# M227X.net
KiCad netlist of a schematic drawn in EAGLE
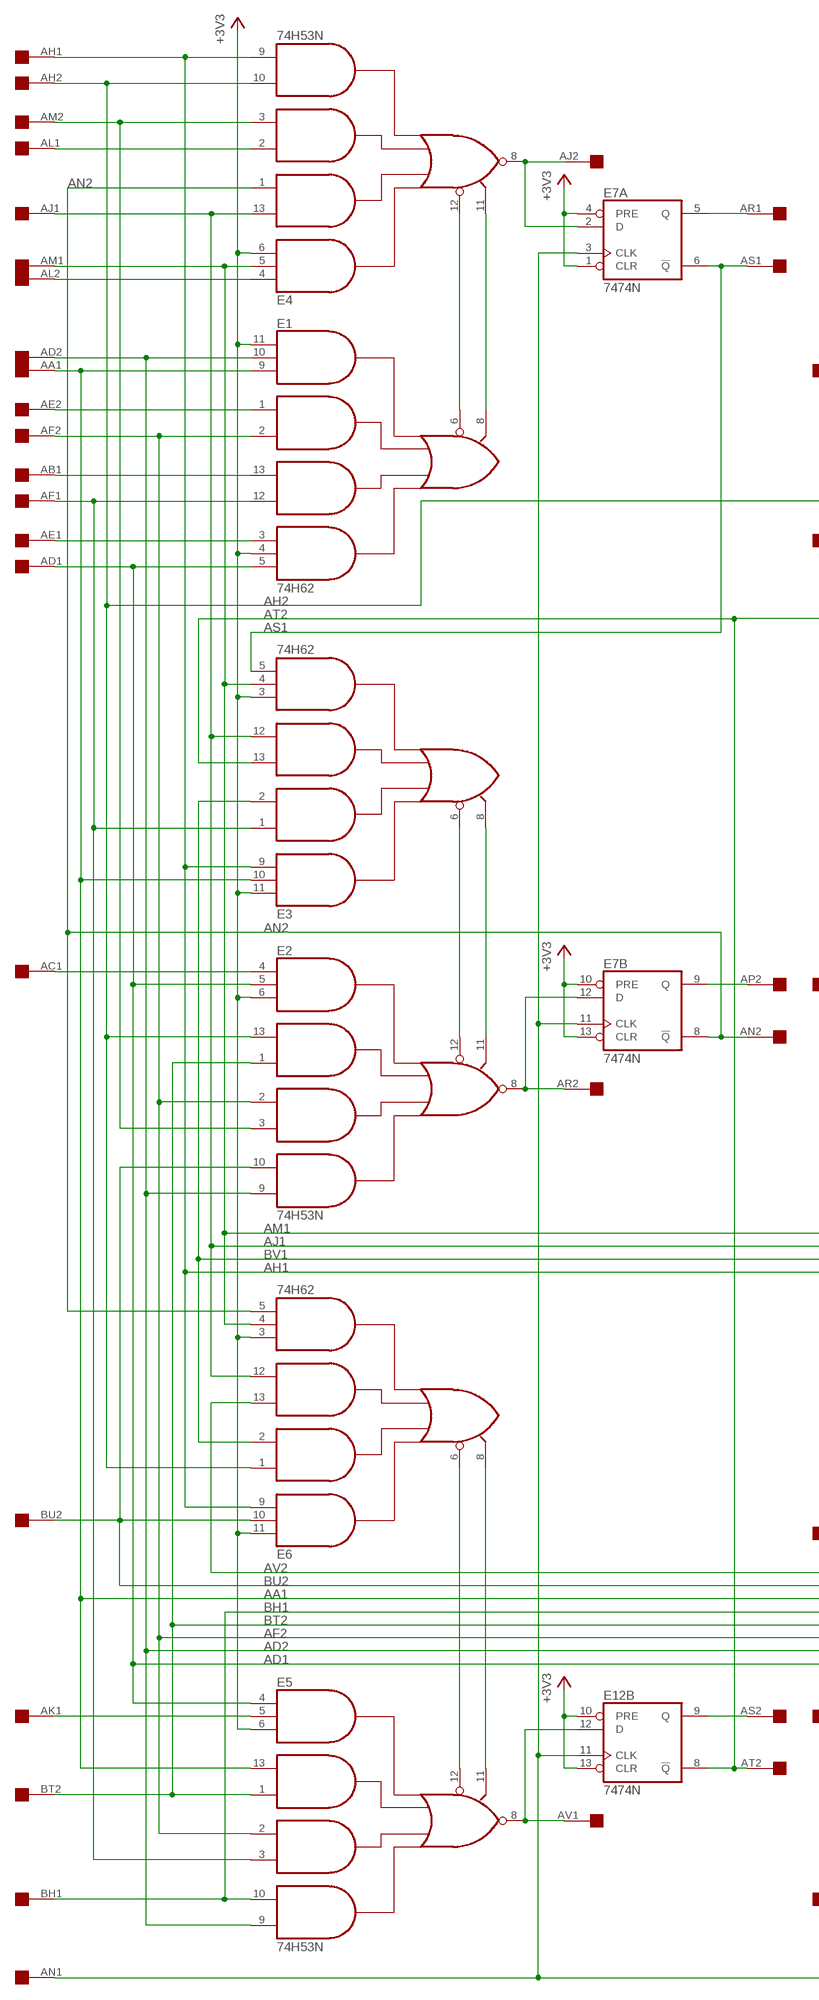
[diagram p0: schematic, sheet 1, part 1 of 2]
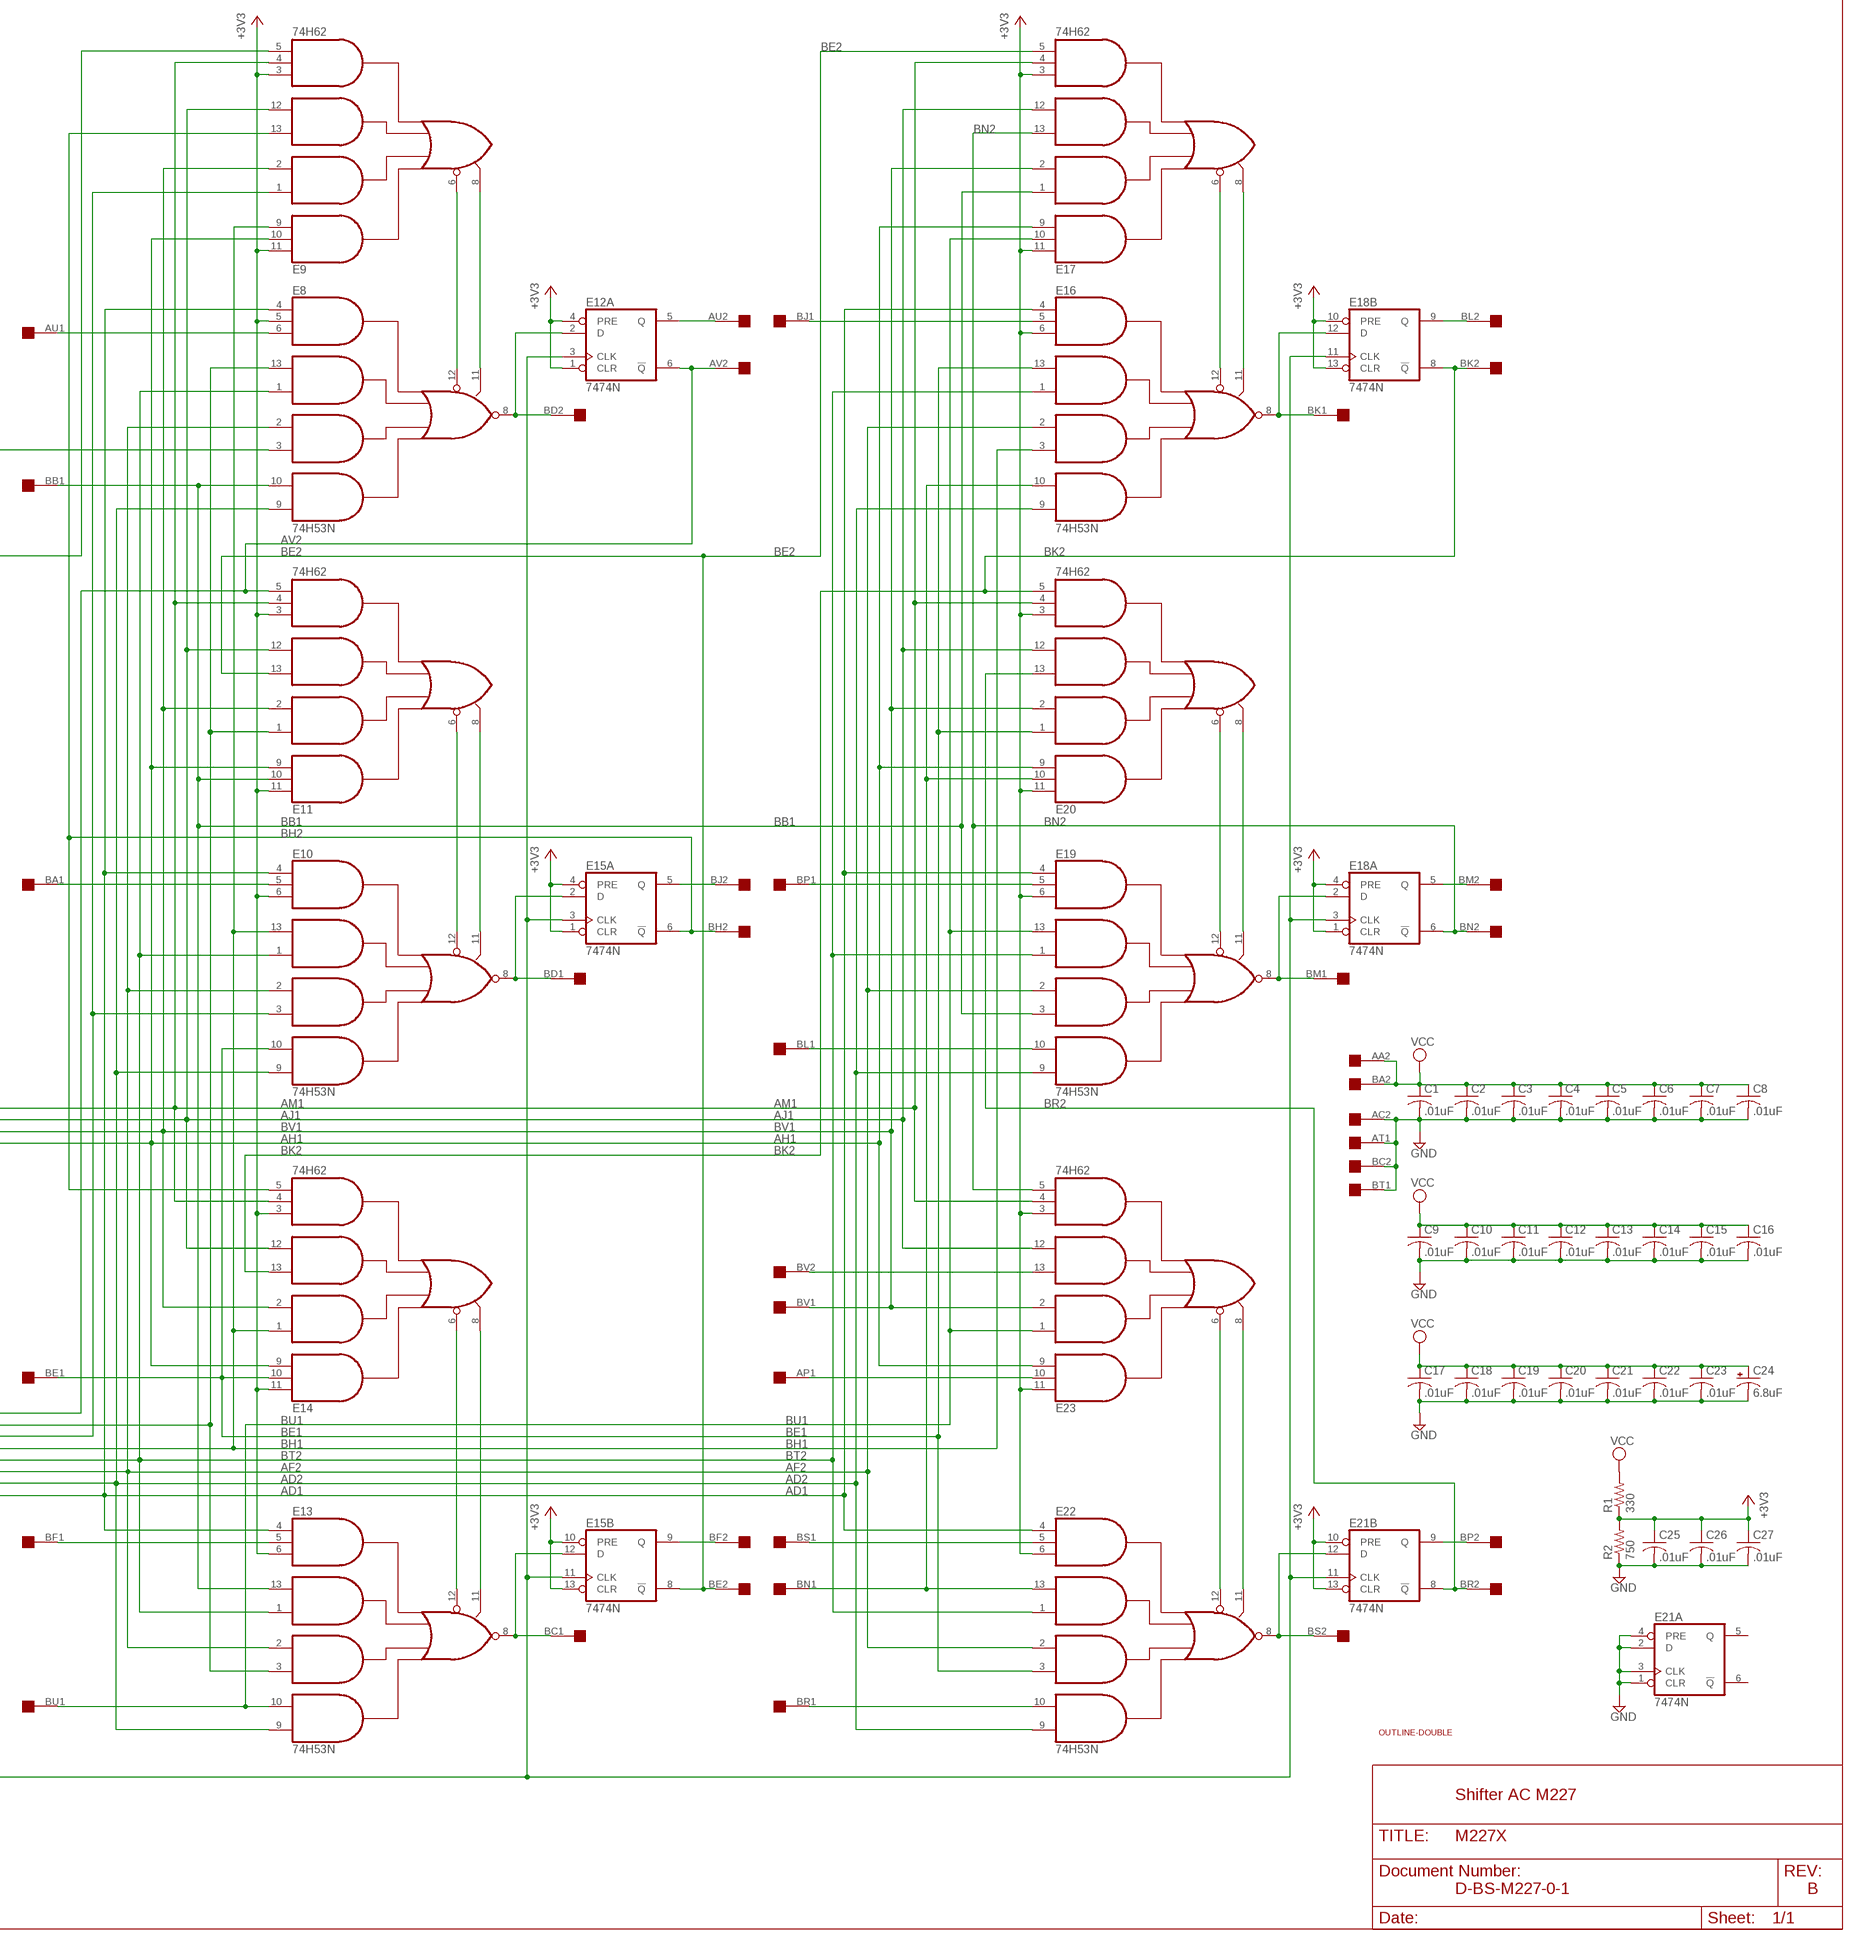
[diagram p1: schematic, sheet 1, part 2 of 2]

(export (version "E")
  (design (tool "Eeschema 10.0.6"))
  (components
    (comp (ref "C1")
      (value ".01uF")
      (footprint "eagle-import:C050-025X075")
      (libsource (lib "eagle-import") (part "C-US050-025X075"))
    )
    (comp (ref "C2")
      (value ".01uF")
      (footprint "eagle-import:C050-025X075")
      (libsource (lib "eagle-import") (part "C-US050-025X075"))
    )
    (comp (ref "C3")
      (value ".01uF")
      (footprint "eagle-import:C050-025X075")
      (libsource (lib "eagle-import") (part "C-US050-025X075"))
    )
    (comp (ref "C4")
      (value ".01uF")
      (footprint "eagle-import:C050-025X075")
      (libsource (lib "eagle-import") (part "C-US050-025X075"))
    )
    (comp (ref "C5")
      (value ".01uF")
      (footprint "eagle-import:C050-025X075")
      (libsource (lib "eagle-import") (part "C-US050-025X075"))
    )
    (comp (ref "C6")
      (value ".01uF")
      (footprint "eagle-import:C050-025X075")
      (libsource (lib "eagle-import") (part "C-US050-025X075"))
    )
    (comp (ref "C7")
      (value ".01uF")
      (footprint "eagle-import:C050-025X075")
      (libsource (lib "eagle-import") (part "C-US050-025X075"))
    )
    (comp (ref "C8")
      (value ".01uF")
      (footprint "eagle-import:C050-025X075")
      (libsource (lib "eagle-import") (part "C-US050-025X075"))
    )
    (comp (ref "C9")
      (value ".01uF")
      (footprint "eagle-import:C050-025X075")
      (libsource (lib "eagle-import") (part "C-US050-025X075"))
    )
    (comp (ref "C10")
      (value ".01uF")
      (footprint "eagle-import:C050-025X075")
      (libsource (lib "eagle-import") (part "C-US050-025X075"))
    )
    (comp (ref "C11")
      (value ".01uF")
      (footprint "eagle-import:C050-025X075")
      (libsource (lib "eagle-import") (part "C-US050-025X075"))
    )
    (comp (ref "C12")
      (value ".01uF")
      (footprint "eagle-import:C050-025X075")
      (libsource (lib "eagle-import") (part "C-US050-025X075"))
    )
    (comp (ref "C13")
      (value ".01uF")
      (footprint "eagle-import:C050-025X075")
      (libsource (lib "eagle-import") (part "C-US050-025X075"))
    )
    (comp (ref "C14")
      (value ".01uF")
      (footprint "eagle-import:C050-025X075")
      (libsource (lib "eagle-import") (part "C-US050-025X075"))
    )
    (comp (ref "C15")
      (value ".01uF")
      (footprint "eagle-import:C050-025X075")
      (libsource (lib "eagle-import") (part "C-US050-025X075"))
    )
    (comp (ref "C16")
      (value ".01uF")
      (footprint "eagle-import:C050-025X075")
      (libsource (lib "eagle-import") (part "C-US050-025X075"))
    )
    (comp (ref "C17")
      (value ".01uF")
      (footprint "eagle-import:C050-025X075")
      (libsource (lib "eagle-import") (part "C-US050-025X075"))
    )
    (comp (ref "C18")
      (value ".01uF")
      (footprint "eagle-import:C050-025X075")
      (libsource (lib "eagle-import") (part "C-US050-025X075"))
    )
    (comp (ref "C19")
      (value ".01uF")
      (footprint "eagle-import:C050-025X075")
      (libsource (lib "eagle-import") (part "C-US050-025X075"))
    )
    (comp (ref "C20")
      (value ".01uF")
      (footprint "eagle-import:C050-025X075")
      (libsource (lib "eagle-import") (part "C-US050-025X075"))
    )
    (comp (ref "C21")
      (value ".01uF")
      (footprint "eagle-import:C050-025X075")
      (libsource (lib "eagle-import") (part "C-US050-025X075"))
    )
    (comp (ref "C22")
      (value ".01uF")
      (footprint "eagle-import:C050-025X075")
      (libsource (lib "eagle-import") (part "C-US050-025X075"))
    )
    (comp (ref "C23")
      (value ".01uF")
      (footprint "eagle-import:C050-025X075")
      (libsource (lib "eagle-import") (part "C-US050-025X075"))
    )
    (comp (ref "C24")
      (value "6.8uF")
      (footprint "eagle-import:E12-8")
      (libsource (lib "eagle-import") (part "CPOL-USE20-8AXIAL"))
    )
    (comp (ref "C25")
      (value ".01uF")
      (footprint "eagle-import:C050-025X075")
      (libsource (lib "eagle-import") (part "C-US050-025X075"))
    )
    (comp (ref "C26")
      (value ".01uF")
      (footprint "eagle-import:C050-025X075")
      (libsource (lib "eagle-import") (part "C-US050-025X075"))
    )
    (comp (ref "C27")
      (value ".01uF")
      (footprint "eagle-import:C050-025X075")
      (libsource (lib "eagle-import") (part "C-US050-025X075"))
    )
    (comp (ref "E1")
      (value "74H62")
      (footprint "eagle-import:DIL14")
      (libsource (lib "eagle-import") (part "7462"))
    )
    (comp (ref "E2")
      (value "74H53N")
      (footprint "eagle-import:DIL14")
      (libsource (lib "eagle-import") (part "74H53N"))
    )
    (comp (ref "E3")
      (value "74H62")
      (footprint "eagle-import:DIL14")
      (libsource (lib "eagle-import") (part "7462"))
    )
    (comp (ref "E4")
      (value "74H53N")
      (footprint "eagle-import:DIL14")
      (libsource (lib "eagle-import") (part "74H53N"))
    )
    (comp (ref "E5")
      (value "74H53N")
      (footprint "eagle-import:DIL14")
      (libsource (lib "eagle-import") (part "74H53N"))
    )
    (comp (ref "E6")
      (value "74H62")
      (footprint "eagle-import:DIL14")
      (libsource (lib "eagle-import") (part "7462"))
    )
    (comp (ref "E7")
      (value "7474N")
      (footprint "eagle-import:DIL14")
      (libsource (lib "eagle-import") (part "7474NS"))
    )
    (comp (ref "E8")
      (value "74H53N")
      (footprint "eagle-import:DIL14")
      (libsource (lib "eagle-import") (part "74H53N"))
    )
    (comp (ref "E9")
      (value "74H62")
      (footprint "eagle-import:DIL14")
      (libsource (lib "eagle-import") (part "7462"))
    )
    (comp (ref "E10")
      (value "74H53N")
      (footprint "eagle-import:DIL14")
      (libsource (lib "eagle-import") (part "74H53N"))
    )
    (comp (ref "E11")
      (value "74H62")
      (footprint "eagle-import:DIL14")
      (libsource (lib "eagle-import") (part "7462"))
    )
    (comp (ref "E12")
      (value "7474N")
      (footprint "eagle-import:DIL14")
      (libsource (lib "eagle-import") (part "7474NS"))
    )
    (comp (ref "E13")
      (value "74H53N")
      (footprint "eagle-import:DIL14")
      (libsource (lib "eagle-import") (part "74H53N"))
    )
    (comp (ref "E14")
      (value "74H62")
      (footprint "eagle-import:DIL14")
      (libsource (lib "eagle-import") (part "7462"))
    )
    (comp (ref "E15")
      (value "7474N")
      (footprint "eagle-import:DIL14")
      (libsource (lib "eagle-import") (part "7474NS"))
    )
    (comp (ref "E16")
      (value "74H53N")
      (footprint "eagle-import:DIL14")
      (libsource (lib "eagle-import") (part "74H53N"))
    )
    (comp (ref "E17")
      (value "74H62")
      (footprint "eagle-import:DIL14")
      (libsource (lib "eagle-import") (part "7462"))
    )
    (comp (ref "E18")
      (value "7474N")
      (footprint "eagle-import:DIL14")
      (libsource (lib "eagle-import") (part "7474NS"))
    )
    (comp (ref "E19")
      (value "74H53N")
      (footprint "eagle-import:DIL14")
      (libsource (lib "eagle-import") (part "74H53N"))
    )
    (comp (ref "E20")
      (value "74H62")
      (footprint "eagle-import:DIL14")
      (libsource (lib "eagle-import") (part "7462"))
    )
    (comp (ref "E21")
      (value "7474N")
      (footprint "eagle-import:DIL14")
      (libsource (lib "eagle-import") (part "7474NS"))
    )
    (comp (ref "E22")
      (value "74H53N")
      (footprint "eagle-import:DIL14")
      (libsource (lib "eagle-import") (part "74H53N"))
    )
    (comp (ref "E23")
      (value "74H62")
      (footprint "eagle-import:DIL14")
      (libsource (lib "eagle-import") (part "7462"))
    )
    (comp (ref "R1")
      (value "330")
      (footprint "eagle-import:0207_10")
      (libsource (lib "eagle-import") (part "R-US_0207/10"))
    )
    (comp (ref "R2")
      (value "750")
      (footprint "eagle-import:0207_10")
      (libsource (lib "eagle-import") (part "R-US_0207/10"))
    )
    (comp (ref "U$1")
      (value "OUTLINE-DOUBLE")
      (footprint "eagle-import:DOUBLE")
      (libsource (lib "eagle-import") (part "OUTLINE-DOUBLE"))
    )
    (comp (ref "U$3")
      (value "DOUBLE")
      (footprint "eagle-import:EDGE-CON4")
      (libsource (lib "eagle-import") (part "DOUBLE"))
    )
  )
  (nets
    (net (code "1") (name "+3V3") (class "Default")
      (node (ref "C25") (pin "1") (pinfunction "1_1") (pintype "passive"))
      (node (ref "C26") (pin "1") (pinfunction "1_1") (pintype "passive"))
      (node (ref "C27") (pin "1") (pinfunction "1_1") (pintype "passive"))
      (node (ref "E1") (pin "11") (pinfunction "I1_11") (pintype "input"))
      (node (ref "E1") (pin "4") (pinfunction "I9_4") (pintype "input"))
      (node (ref "E10") (pin "6") (pinfunction "I2_6") (pintype "input"))
      (node (ref "E11") (pin "11") (pinfunction "I1_11") (pintype "input"))
      (node (ref "E11") (pin "3") (pinfunction "I8_3") (pintype "input"))
      (node (ref "E12") (pin "1") (pinfunction "CLR_1") (pintype "input"))
      (node (ref "E12") (pin "10") (pinfunction "PRE_10") (pintype "input"))
      (node (ref "E12") (pin "13") (pinfunction "CLR_13") (pintype "input"))
      (node (ref "E12") (pin "4") (pinfunction "PRE_4") (pintype "input"))
      (node (ref "E13") (pin "6") (pinfunction "I2_6") (pintype "input"))
      (node (ref "E14") (pin "11") (pinfunction "I1_11") (pintype "input"))
      (node (ref "E14") (pin "3") (pinfunction "I8_3") (pintype "input"))
      (node (ref "E15") (pin "1") (pinfunction "CLR_1") (pintype "input"))
      (node (ref "E15") (pin "10") (pinfunction "PRE_10") (pintype "input"))
      (node (ref "E15") (pin "13") (pinfunction "CLR_13") (pintype "input"))
      (node (ref "E15") (pin "4") (pinfunction "PRE_4") (pintype "input"))
      (node (ref "E16") (pin "6") (pinfunction "I2_6") (pintype "input"))
      (node (ref "E17") (pin "11") (pinfunction "I1_11") (pintype "input"))
      (node (ref "E17") (pin "3") (pinfunction "I8_3") (pintype "input"))
      (node (ref "E18") (pin "1") (pinfunction "CLR_1") (pintype "input"))
      (node (ref "E18") (pin "10") (pinfunction "PRE_10") (pintype "input"))
      (node (ref "E18") (pin "13") (pinfunction "CLR_13") (pintype "input"))
      (node (ref "E18") (pin "4") (pinfunction "PRE_4") (pintype "input"))
      (node (ref "E19") (pin "6") (pinfunction "I2_6") (pintype "input"))
      (node (ref "E2") (pin "6") (pinfunction "I2_6") (pintype "input"))
      (node (ref "E20") (pin "11") (pinfunction "I1_11") (pintype "input"))
      (node (ref "E20") (pin "3") (pinfunction "I8_3") (pintype "input"))
      (node (ref "E21") (pin "10") (pinfunction "PRE_10") (pintype "input"))
      (node (ref "E21") (pin "13") (pinfunction "CLR_13") (pintype "input"))
      (node (ref "E22") (pin "6") (pinfunction "I2_6") (pintype "input"))
      (node (ref "E23") (pin "11") (pinfunction "I1_11") (pintype "input"))
      (node (ref "E23") (pin "3") (pinfunction "I8_3") (pintype "input"))
      (node (ref "E3") (pin "11") (pinfunction "I1_11") (pintype "input"))
      (node (ref "E3") (pin "3") (pinfunction "I8_3") (pintype "input"))
      (node (ref "E4") (pin "6") (pinfunction "I2_6") (pintype "input"))
      (node (ref "E5") (pin "6") (pinfunction "I2_6") (pintype "input"))
      (node (ref "E6") (pin "11") (pinfunction "I1_11") (pintype "input"))
      (node (ref "E6") (pin "3") (pinfunction "I8_3") (pintype "input"))
      (node (ref "E7") (pin "1") (pinfunction "CLR_1") (pintype "input"))
      (node (ref "E7") (pin "10") (pinfunction "PRE_10") (pintype "input"))
      (node (ref "E7") (pin "13") (pinfunction "CLR_13") (pintype "input"))
      (node (ref "E7") (pin "4") (pinfunction "PRE_4") (pintype "input"))
      (node (ref "E8") (pin "5") (pinfunction "I11_5") (pintype "input"))
      (node (ref "E9") (pin "11") (pinfunction "I1_11") (pintype "input"))
      (node (ref "E9") (pin "3") (pinfunction "I8_3") (pintype "input"))
      (node (ref "R1") (pin "1") (pinfunction "1_1") (pintype "passive"))
      (node (ref "R2") (pin "2") (pinfunction "2_2") (pintype "passive"))
    )
    (net (code "2") (name "/AA1") (class "Default")
      (node (ref "E1") (pin "9") (pinfunction "I3_9") (pintype "input"))
      (node (ref "E10") (pin "3") (pinfunction "I6_3") (pintype "input"))
      (node (ref "E3") (pin "10") (pinfunction "I2_10") (pintype "input"))
      (node (ref "E5") (pin "13") (pinfunction "I3_13") (pintype "input"))
      (node (ref "E9") (pin "1") (pinfunction "I4_1") (pintype "input"))
      (node (ref "U$3") (pin "AA1") (pinfunction "1_AA1") (pintype "bidirectional"))
    )
    (net (code "3") (name "/AD1") (class "Default")
      (node (ref "E1") (pin "5") (pinfunction "I10_5") (pintype "input"))
      (node (ref "E10") (pin "4") (pinfunction "I1_4") (pintype "input"))
      (node (ref "E13") (pin "4") (pinfunction "I1_4") (pintype "input"))
      (node (ref "E16") (pin "4") (pinfunction "I1_4") (pintype "input"))
      (node (ref "E19") (pin "4") (pinfunction "I1_4") (pintype "input"))
      (node (ref "E2") (pin "5") (pinfunction "I11_5") (pintype "input"))
      (node (ref "E22") (pin "4") (pinfunction "I1_4") (pintype "input"))
      (node (ref "E5") (pin "4") (pinfunction "I1_4") (pintype "input"))
      (node (ref "E8") (pin "4") (pinfunction "I1_4") (pintype "input"))
      (node (ref "U$3") (pin "AD1") (pinfunction "1_AD1") (pintype "bidirectional"))
    )
    (net (code "4") (name "/AD2") (class "Default")
      (node (ref "E1") (pin "10") (pinfunction "I2_10") (pintype "input"))
      (node (ref "E10") (pin "9") (pinfunction "I8_9") (pintype "input"))
      (node (ref "E13") (pin "9") (pinfunction "I8_9") (pintype "input"))
      (node (ref "E16") (pin "9") (pinfunction "I8_9") (pintype "input"))
      (node (ref "E19") (pin "9") (pinfunction "I8_9") (pintype "input"))
      (node (ref "E2") (pin "9") (pinfunction "I8_9") (pintype "input"))
      (node (ref "E22") (pin "9") (pinfunction "I8_9") (pintype "input"))
      (node (ref "E5") (pin "9") (pinfunction "I8_9") (pintype "input"))
      (node (ref "E8") (pin "9") (pinfunction "I8_9") (pintype "input"))
      (node (ref "U$3") (pin "AD2") (pinfunction "1_AD2") (pintype "bidirectional"))
    )
    (net (code "5") (name "/AF2") (class "Default")
      (node (ref "E1") (pin "2") (pinfunction "I5_2") (pintype "input"))
      (node (ref "E10") (pin "2") (pinfunction "I5_2") (pintype "input"))
      (node (ref "E13") (pin "2") (pinfunction "I5_2") (pintype "input"))
      (node (ref "E16") (pin "2") (pinfunction "I5_2") (pintype "input"))
      (node (ref "E19") (pin "2") (pinfunction "I5_2") (pintype "input"))
      (node (ref "E2") (pin "2") (pinfunction "I5_2") (pintype "input"))
      (node (ref "E22") (pin "2") (pinfunction "I5_2") (pintype "input"))
      (node (ref "E5") (pin "2") (pinfunction "I5_2") (pintype "input"))
      (node (ref "E8") (pin "2") (pinfunction "I5_2") (pintype "input"))
      (node (ref "U$3") (pin "AF2") (pinfunction "1_AF2") (pintype "bidirectional"))
    )
    (net (code "6") (name "/AH1") (class "Default")
      (node (ref "E11") (pin "9") (pinfunction "I3_9") (pintype "input"))
      (node (ref "E14") (pin "9") (pinfunction "I3_9") (pintype "input"))
      (node (ref "E17") (pin "9") (pinfunction "I3_9") (pintype "input"))
      (node (ref "E20") (pin "9") (pinfunction "I3_9") (pintype "input"))
      (node (ref "E23") (pin "9") (pinfunction "I3_9") (pintype "input"))
      (node (ref "E3") (pin "9") (pinfunction "I3_9") (pintype "input"))
      (node (ref "E4") (pin "9") (pinfunction "I8_9") (pintype "input"))
      (node (ref "E6") (pin "9") (pinfunction "I3_9") (pintype "input"))
      (node (ref "E9") (pin "10") (pinfunction "I2_10") (pintype "input"))
      (node (ref "U$3") (pin "AH1") (pinfunction "1_AH1") (pintype "bidirectional"))
    )
    (net (code "7") (name "/AH2") (class "Default")
      (node (ref "E2") (pin "13") (pinfunction "I3_13") (pintype "input"))
      (node (ref "E4") (pin "10") (pinfunction "I7_10") (pintype "input"))
      (node (ref "E6") (pin "1") (pinfunction "I4_1") (pintype "input"))
      (node (ref "E8") (pin "3") (pinfunction "I6_3") (pintype "input"))
      (node (ref "U$3") (pin "AH2") (pinfunction "1_AH2") (pintype "bidirectional"))
    )
    (net (code "8") (name "/AJ1") (class "Default")
      (node (ref "E11") (pin "12") (pinfunction "I7_12") (pintype "input"))
      (node (ref "E14") (pin "12") (pinfunction "I7_12") (pintype "input"))
      (node (ref "E17") (pin "12") (pinfunction "I7_12") (pintype "input"))
      (node (ref "E20") (pin "12") (pinfunction "I7_12") (pintype "input"))
      (node (ref "E23") (pin "12") (pinfunction "I7_12") (pintype "input"))
      (node (ref "E3") (pin "12") (pinfunction "I7_12") (pintype "input"))
      (node (ref "E4") (pin "13") (pinfunction "I3_13") (pintype "input"))
      (node (ref "E6") (pin "12") (pinfunction "I7_12") (pintype "input"))
      (node (ref "E9") (pin "12") (pinfunction "I7_12") (pintype "input"))
      (node (ref "U$3") (pin "AJ1") (pinfunction "1_AJ1") (pintype "bidirectional"))
    )
    (net (code "9") (name "/AM1") (class "Default")
      (node (ref "E11") (pin "4") (pinfunction "I9_4") (pintype "input"))
      (node (ref "E14") (pin "4") (pinfunction "I9_4") (pintype "input"))
      (node (ref "E17") (pin "4") (pinfunction "I9_4") (pintype "input"))
      (node (ref "E20") (pin "4") (pinfunction "I9_4") (pintype "input"))
      (node (ref "E23") (pin "4") (pinfunction "I9_4") (pintype "input"))
      (node (ref "E3") (pin "4") (pinfunction "I9_4") (pintype "input"))
      (node (ref "E4") (pin "5") (pinfunction "I11_5") (pintype "input"))
      (node (ref "E6") (pin "4") (pinfunction "I9_4") (pintype "input"))
      (node (ref "E9") (pin "4") (pinfunction "I9_4") (pintype "input"))
      (node (ref "U$3") (pin "AM1") (pinfunction "1_AM1") (pintype "bidirectional"))
    )
    (net (code "10") (name "/AN2") (class "Default")
      (node (ref "E4") (pin "1") (pinfunction "I4_1") (pintype "input"))
      (node (ref "E6") (pin "5") (pinfunction "I10_5") (pintype "input"))
      (node (ref "E7") (pin "8") (pinfunction "~{Q}_8") (pintype "output"))
      (node (ref "U$3") (pin "AN2") (pinfunction "1_AN2") (pintype "bidirectional"))
    )
    (net (code "11") (name "/AS1") (class "Default")
      (node (ref "E3") (pin "5") (pinfunction "I10_5") (pintype "input"))
      (node (ref "E7") (pin "6") (pinfunction "~{Q}_6") (pintype "output"))
      (node (ref "U$3") (pin "AS1") (pinfunction "1_AS1") (pintype "bidirectional"))
    )
    (net (code "12") (name "/AT2") (class "Default")
      (node (ref "E12") (pin "8") (pinfunction "~{Q}_8") (pintype "output"))
      (node (ref "E3") (pin "13") (pinfunction "I6_13") (pintype "input"))
      (node (ref "E9") (pin "5") (pinfunction "I10_5") (pintype "input"))
      (node (ref "U$3") (pin "AT2") (pinfunction "1_AT2") (pintype "bidirectional"))
    )
    (net (code "13") (name "/AV2") (class "Default")
      (node (ref "E11") (pin "5") (pinfunction "I10_5") (pintype "input"))
      (node (ref "E12") (pin "6") (pinfunction "~{Q}_6") (pintype "output"))
      (node (ref "E6") (pin "13") (pinfunction "I6_13") (pintype "input"))
      (node (ref "U$3") (pin "AV2") (pinfunction "1_AV2") (pintype "bidirectional"))
    )
    (net (code "14") (name "/BB1") (class "Default")
      (node (ref "E11") (pin "10") (pinfunction "I2_10") (pintype "input"))
      (node (ref "E13") (pin "13") (pinfunction "I3_13") (pintype "input"))
      (node (ref "E17") (pin "1") (pinfunction "I4_1") (pintype "input"))
      (node (ref "E19") (pin "3") (pinfunction "I6_3") (pintype "input"))
      (node (ref "E8") (pin "10") (pinfunction "I7_10") (pintype "input"))
      (node (ref "U$3") (pin "BB1") (pinfunction "1_BB1") (pintype "bidirectional"))
    )
    (net (code "15") (name "/BE1") (class "Default")
      (node (ref "E10") (pin "10") (pinfunction "I7_10") (pintype "input"))
      (node (ref "E14") (pin "10") (pinfunction "I2_10") (pintype "input"))
      (node (ref "E16") (pin "13") (pinfunction "I3_13") (pintype "input"))
      (node (ref "E20") (pin "1") (pinfunction "I4_1") (pintype "input"))
      (node (ref "E22") (pin "3") (pinfunction "I6_3") (pintype "input"))
      (node (ref "U$3") (pin "BE1") (pinfunction "1_BE1") (pintype "bidirectional"))
    )
    (net (code "16") (name "/BE2") (class "Default")
      (node (ref "E11") (pin "13") (pinfunction "I6_13") (pintype "input"))
      (node (ref "E15") (pin "8") (pinfunction "~{Q}_8") (pintype "output"))
      (node (ref "E17") (pin "5") (pinfunction "I10_5") (pintype "input"))
      (node (ref "U$3") (pin "BE2") (pinfunction "1_BE2") (pintype "bidirectional"))
    )
    (net (code "17") (name "/BH1") (class "Default")
      (node (ref "E10") (pin "13") (pinfunction "I3_13") (pintype "input"))
      (node (ref "E14") (pin "1") (pinfunction "I4_1") (pintype "input"))
      (node (ref "E16") (pin "3") (pinfunction "I6_3") (pintype "input"))
      (node (ref "E5") (pin "10") (pinfunction "I7_10") (pintype "input"))
      (node (ref "E9") (pin "9") (pinfunction "I3_9") (pintype "input"))
      (node (ref "U$3") (pin "BH1") (pinfunction "1_BH1") (pintype "bidirectional"))
    )
    (net (code "18") (name "/BH2") (class "Default")
      (node (ref "E14") (pin "5") (pinfunction "I10_5") (pintype "input"))
      (node (ref "E15") (pin "6") (pinfunction "~{Q}_6") (pintype "output"))
      (node (ref "E9") (pin "13") (pinfunction "I6_13") (pintype "input"))
      (node (ref "U$3") (pin "BH2") (pinfunction "1_BH2") (pintype "bidirectional"))
    )
    (net (code "19") (name "/BK2") (class "Default")
      (node (ref "E14") (pin "13") (pinfunction "I6_13") (pintype "input"))
      (node (ref "E18") (pin "8") (pinfunction "~{Q}_8") (pintype "output"))
      (node (ref "E20") (pin "5") (pinfunction "I10_5") (pintype "input"))
      (node (ref "U$3") (pin "BK2") (pinfunction "1_BK2") (pintype "bidirectional"))
    )
    (net (code "20") (name "/BN2") (class "Default")
      (node (ref "E17") (pin "13") (pinfunction "I6_13") (pintype "input"))
      (node (ref "E18") (pin "6") (pinfunction "~{Q}_6") (pintype "output"))
      (node (ref "E23") (pin "5") (pinfunction "I10_5") (pintype "input"))
      (node (ref "U$3") (pin "BN2") (pinfunction "1_BN2") (pintype "bidirectional"))
    )
    (net (code "21") (name "/BR2") (class "Default")
      (node (ref "E20") (pin "13") (pinfunction "I6_13") (pintype "input"))
      (node (ref "E21") (pin "8") (pinfunction "~{Q}_8") (pintype "output"))
      (node (ref "U$3") (pin "BR2") (pinfunction "1_BR2") (pintype "bidirectional"))
    )
    (net (code "22") (name "/BT2") (class "Default")
      (node (ref "E10") (pin "1") (pinfunction "I4_1") (pintype "input"))
      (node (ref "E13") (pin "1") (pinfunction "I4_1") (pintype "input"))
      (node (ref "E16") (pin "1") (pinfunction "I4_1") (pintype "input"))
      (node (ref "E19") (pin "1") (pinfunction "I4_1") (pintype "input"))
      (node (ref "E2") (pin "1") (pinfunction "I4_1") (pintype "input"))
      (node (ref "E22") (pin "1") (pinfunction "I4_1") (pintype "input"))
      (node (ref "E5") (pin "1") (pinfunction "I4_1") (pintype "input"))
      (node (ref "E8") (pin "1") (pinfunction "I4_1") (pintype "input"))
      (node (ref "U$3") (pin "BT2") (pinfunction "1_BT2") (pintype "bidirectional"))
    )
    (net (code "23") (name "/BU1") (class "Default")
      (node (ref "E13") (pin "10") (pinfunction "I7_10") (pintype "input"))
      (node (ref "E17") (pin "10") (pinfunction "I2_10") (pintype "input"))
      (node (ref "E19") (pin "13") (pinfunction "I3_13") (pintype "input"))
      (node (ref "E23") (pin "1") (pinfunction "I4_1") (pintype "input"))
      (node (ref "U$3") (pin "BU1") (pinfunction "1_BU1") (pintype "bidirectional"))
    )
    (net (code "24") (name "/BU2") (class "Default")
      (node (ref "E11") (pin "1") (pinfunction "I4_1") (pintype "input"))
      (node (ref "E13") (pin "3") (pinfunction "I6_3") (pintype "input"))
      (node (ref "E2") (pin "10") (pinfunction "I7_10") (pintype "input"))
      (node (ref "E6") (pin "10") (pinfunction "I2_10") (pintype "input"))
      (node (ref "E8") (pin "13") (pinfunction "I3_13") (pintype "input"))
      (node (ref "U$3") (pin "BU2") (pinfunction "1_BU2") (pintype "bidirectional"))
    )
    (net (code "25") (name "/BV1") (class "Default")
      (node (ref "E11") (pin "2") (pinfunction "I5_2") (pintype "input"))
      (node (ref "E14") (pin "2") (pinfunction "I5_2") (pintype "input"))
      (node (ref "E17") (pin "2") (pinfunction "I5_2") (pintype "input"))
      (node (ref "E20") (pin "2") (pinfunction "I5_2") (pintype "input"))
      (node (ref "E23") (pin "2") (pinfunction "I5_2") (pintype "input"))
      (node (ref "E3") (pin "2") (pinfunction "I5_2") (pintype "input"))
      (node (ref "E6") (pin "2") (pinfunction "I5_2") (pintype "input"))
      (node (ref "E9") (pin "2") (pinfunction "I5_2") (pintype "input"))
      (node (ref "U$3") (pin "BV1") (pinfunction "1_BV1") (pintype "bidirectional"))
    )
    (net (code "26") (name "GND") (class "Default")
      (node (ref "C1") (pin "2") (pinfunction "2_2") (pintype "passive"))
      (node (ref "C10") (pin "2") (pinfunction "2_2") (pintype "passive"))
      (node (ref "C11") (pin "2") (pinfunction "2_2") (pintype "passive"))
      (node (ref "C12") (pin "2") (pinfunction "2_2") (pintype "passive"))
      (node (ref "C13") (pin "2") (pinfunction "2_2") (pintype "passive"))
      (node (ref "C14") (pin "2") (pinfunction "2_2") (pintype "passive"))
      (node (ref "C15") (pin "2") (pinfunction "2_2") (pintype "passive"))
      (node (ref "C16") (pin "2") (pinfunction "2_2") (pintype "passive"))
      (node (ref "C17") (pin "2") (pinfunction "2_2") (pintype "passive"))
      (node (ref "C18") (pin "2") (pinfunction "2_2") (pintype "passive"))
      (node (ref "C19") (pin "2") (pinfunction "2_2") (pintype "passive"))
      (node (ref "C2") (pin "2") (pinfunction "2_2") (pintype "passive"))
      (node (ref "C20") (pin "2") (pinfunction "2_2") (pintype "passive"))
      (node (ref "C21") (pin "2") (pinfunction "2_2") (pintype "passive"))
      (node (ref "C22") (pin "2") (pinfunction "2_2") (pintype "passive"))
      (node (ref "C23") (pin "2") (pinfunction "2_2") (pintype "passive"))
      (node (ref "C24") (pin "-") (pinfunction "-_-") (pintype "passive"))
      (node (ref "C25") (pin "2") (pinfunction "2_2") (pintype "passive"))
      (node (ref "C26") (pin "2") (pinfunction "2_2") (pintype "passive"))
      (node (ref "C27") (pin "2") (pinfunction "2_2") (pintype "passive"))
      (node (ref "C3") (pin "2") (pinfunction "2_2") (pintype "passive"))
      (node (ref "C4") (pin "2") (pinfunction "2_2") (pintype "passive"))
      (node (ref "C5") (pin "2") (pinfunction "2_2") (pintype "passive"))
      (node (ref "C6") (pin "2") (pinfunction "2_2") (pintype "passive"))
      (node (ref "C7") (pin "2") (pinfunction "2_2") (pintype "passive"))
      (node (ref "C8") (pin "2") (pinfunction "2_2") (pintype "passive"))
      (node (ref "C9") (pin "2") (pinfunction "2_2") (pintype "passive"))
      (node (ref "E21") (pin "1") (pinfunction "CLR_1") (pintype "input"))
      (node (ref "E21") (pin "2") (pinfunction "D_2") (pintype "input"))
      (node (ref "E21") (pin "3") (pinfunction "CLK_3") (pintype "input"))
      (node (ref "E21") (pin "4") (pinfunction "PRE_4") (pintype "input"))
      (node (ref "R2") (pin "1") (pinfunction "1_1") (pintype "passive"))
      (node (ref "U$3") (pin "AC2") (pinfunction "1_AC2") (pintype "bidirectional"))
      (node (ref "U$3") (pin "AT1") (pinfunction "1_AT1") (pintype "bidirectional"))
      (node (ref "U$3") (pin "BC2") (pinfunction "1_BC2") (pintype "bidirectional"))
      (node (ref "U$3") (pin "BT1") (pinfunction "1_BT1") (pintype "bidirectional"))
    )
    (net (code "27") (name "Net-(E1A-E0)") (class "Default")
      (node (ref "E1") (pin "6") (pinfunction "E0_6") (pintype "passive"))
      (node (ref "E4") (pin "12") (pinfunction "I9_12") (pintype "passive"))
    )
    (net (code "28") (name "Net-(E1A-E1)") (class "Default")
      (node (ref "E1") (pin "8") (pinfunction "E1_8") (pintype "passive"))
      (node (ref "E4") (pin "11") (pinfunction "I10_11") (pintype "passive"))
    )
    (net (code "29") (name "Net-(E1A-I4)") (class "Default")
      (node (ref "E1") (pin "1") (pinfunction "I4_1") (pintype "input"))
      (node (ref "U$3") (pin "AE2") (pinfunction "1_AE2") (pintype "bidirectional"))
    )
    (net (code "30") (name "Net-(E1A-I6)") (class "Default")
      (node (ref "E1") (pin "13") (pinfunction "I6_13") (pintype "input"))
      (node (ref "U$3") (pin "AB1") (pinfunction "1_AB1") (pintype "bidirectional"))
    )
    (net (code "31") (name "Net-(E1A-I7)") (class "Default")
      (node (ref "E1") (pin "12") (pinfunction "I7_12") (pintype "input"))
      (node (ref "E3") (pin "1") (pinfunction "I4_1") (pintype "input"))
      (node (ref "E5") (pin "3") (pinfunction "I6_3") (pintype "input"))
      (node (ref "U$3") (pin "AF1") (pinfunction "1_AF1") (pintype "bidirectional"))
    )
    (net (code "32") (name "Net-(E1A-I8)") (class "Default")
      (node (ref "E1") (pin "3") (pinfunction "I8_3") (pintype "input"))
      (node (ref "U$3") (pin "AE1") (pinfunction "1_AE1") (pintype "bidirectional"))
    )
    (net (code "33") (name "Net-(E2A-I1)") (class "Default")
      (node (ref "E2") (pin "4") (pinfunction "I1_4") (pintype "input"))
      (node (ref "U$3") (pin "AC1") (pinfunction "1_AC1") (pintype "bidirectional"))
    )
    (net (code "34") (name "Net-(E2A-I6)") (class "Default")
      (node (ref "E2") (pin "3") (pinfunction "I6_3") (pintype "input"))
      (node (ref "E4") (pin "3") (pinfunction "I6_3") (pintype "input"))
      (node (ref "U$3") (pin "AM2") (pinfunction "1_AM2") (pintype "bidirectional"))
    )
    (net (code "35") (name "Net-(E2A-I9)") (class "Default")
      (node (ref "E2") (pin "12") (pinfunction "I9_12") (pintype "passive"))
      (node (ref "E3") (pin "6") (pinfunction "E0_6") (pintype "passive"))
    )
    (net (code "36") (name "Net-(E2A-I10)") (class "Default")
      (node (ref "E2") (pin "11") (pinfunction "I10_11") (pintype "passive"))
      (node (ref "E3") (pin "8") (pinfunction "E1_8") (pintype "passive"))
    )
    (net (code "37") (name "Net-(E2A-O)") (class "Default")
      (node (ref "E2") (pin "8") (pinfunction "O_8") (pintype "output"))
      (node (ref "E7") (pin "12") (pinfunction "D_12") (pintype "input"))
      (node (ref "U$3") (pin "AR2") (pinfunction "1_AR2") (pintype "bidirectional"))
    )
    (net (code "38") (name "Net-(E4A-I1)") (class "Default")
      (node (ref "E4") (pin "4") (pinfunction "I1_4") (pintype "input"))
      (node (ref "U$3") (pin "AL2") (pinfunction "1_AL2") (pintype "bidirectional"))
    )
    (net (code "39") (name "Net-(E4A-I5)") (class "Default")
      (node (ref "E4") (pin "2") (pinfunction "I5_2") (pintype "input"))
      (node (ref "U$3") (pin "AL1") (pinfunction "1_AL1") (pintype "bidirectional"))
    )
    (net (code "40") (name "Net-(E4A-O)") (class "Default")
      (node (ref "E4") (pin "8") (pinfunction "O_8") (pintype "output"))
      (node (ref "E7") (pin "2") (pinfunction "D_2") (pintype "input"))
      (node (ref "U$3") (pin "AJ2") (pinfunction "1_AJ2") (pintype "bidirectional"))
    )
    (net (code "41") (name "Net-(E5A-I9)") (class "Default")
      (node (ref "E5") (pin "12") (pinfunction "I9_12") (pintype "passive"))
      (node (ref "E6") (pin "6") (pinfunction "E0_6") (pintype "passive"))
    )
    (net (code "42") (name "Net-(E5A-I10)") (class "Default")
      (node (ref "E5") (pin "11") (pinfunction "I10_11") (pintype "passive"))
      (node (ref "E6") (pin "8") (pinfunction "E1_8") (pintype "passive"))
    )
    (net (code "43") (name "Net-(E5A-I11)") (class "Default")
      (node (ref "E5") (pin "5") (pinfunction "I11_5") (pintype "input"))
      (node (ref "U$3") (pin "AK1") (pinfunction "1_AK1") (pintype "bidirectional"))
    )
    (net (code "44") (name "Net-(E7A-Q)") (class "Default")
      (node (ref "E7") (pin "5") (pinfunction "Q_5") (pintype "output"))
      (node (ref "U$3") (pin "AR1") (pinfunction "1_AR1") (pintype "bidirectional"))
    )
    (net (code "45") (name "Net-(E7B-Q)") (class "Default")
      (node (ref "E7") (pin "9") (pinfunction "Q_9") (pintype "output"))
      (node (ref "U$3") (pin "AP2") (pinfunction "1_AP2") (pintype "bidirectional"))
    )
    (net (code "46") (name "Net-(E8A-I2)") (class "Default")
      (node (ref "E8") (pin "6") (pinfunction "I2_6") (pintype "input"))
      (node (ref "U$3") (pin "AU1") (pinfunction "1_AU1") (pintype "bidirectional"))
    )
    (net (code "47") (name "Net-(E8A-I9)") (class "Default")
      (node (ref "E8") (pin "12") (pinfunction "I9_12") (pintype "passive"))
      (node (ref "E9") (pin "6") (pinfunction "E0_6") (pintype "passive"))
    )
    (net (code "48") (name "Net-(E8A-I10)") (class "Default")
      (node (ref "E8") (pin "11") (pinfunction "I10_11") (pintype "passive"))
      (node (ref "E9") (pin "8") (pinfunction "E1_8") (pintype "passive"))
    )
    (net (code "49") (name "Net-(E10A-I9)") (class "Default")
      (node (ref "E10") (pin "12") (pinfunction "I9_12") (pintype "passive"))
      (node (ref "E11") (pin "6") (pinfunction "E0_6") (pintype "passive"))
    )
    (net (code "50") (name "Net-(E10A-I10)") (class "Default")
      (node (ref "E10") (pin "11") (pinfunction "I10_11") (pintype "passive"))
      (node (ref "E11") (pin "8") (pinfunction "E1_8") (pintype "passive"))
    )
    (net (code "51") (name "Net-(E10A-I11)") (class "Default")
      (node (ref "E10") (pin "5") (pinfunction "I11_5") (pintype "input"))
      (node (ref "U$3") (pin "BA1") (pinfunction "1_BA1") (pintype "bidirectional"))
    )
    (net (code "52") (name "Net-(E10A-O)") (class "Default")
      (node (ref "E10") (pin "8") (pinfunction "O_8") (pintype "output"))
      (node (ref "E15") (pin "2") (pinfunction "D_2") (pintype "input"))
      (node (ref "U$3") (pin "BD1") (pinfunction "1_BD1") (pintype "bidirectional"))
    )
    (net (code "53") (name "Net-(E12A-CLK)") (class "Default")
      (node (ref "E12") (pin "11") (pinfunction "CLK_11") (pintype "input"))
      (node (ref "E12") (pin "3") (pinfunction "CLK_3") (pintype "input"))
      (node (ref "E15") (pin "11") (pinfunction "CLK_11") (pintype "input"))
      (node (ref "E15") (pin "3") (pinfunction "CLK_3") (pintype "input"))
      (node (ref "E18") (pin "11") (pinfunction "CLK_11") (pintype "input"))
      (node (ref "E18") (pin "3") (pinfunction "CLK_3") (pintype "input"))
      (node (ref "E21") (pin "11") (pinfunction "CLK_11") (pintype "input"))
      (node (ref "E7") (pin "11") (pinfunction "CLK_11") (pintype "input"))
      (node (ref "E7") (pin "3") (pinfunction "CLK_3") (pintype "input"))
      (node (ref "U$3") (pin "AN1") (pinfunction "1_AN1") (pintype "bidirectional"))
    )
    (net (code "54") (name "Net-(E12A-D)") (class "Default")
      (node (ref "E12") (pin "2") (pinfunction "D_2") (pintype "input"))
      (node (ref "E8") (pin "8") (pinfunction "O_8") (pintype "output"))
      (node (ref "U$3") (pin "BD2") (pinfunction "1_BD2") (pintype "bidirectional"))
    )
    (net (code "55") (name "Net-(E12A-Q)") (class "Default")
      (node (ref "E12") (pin "5") (pinfunction "Q_5") (pintype "output"))
      (node (ref "U$3") (pin "AU2") (pinfunction "1_AU2") (pintype "bidirectional"))
    )
    (net (code "56") (name "Net-(E12B-D)") (class "Default")
      (node (ref "E12") (pin "12") (pinfunction "D_12") (pintype "input"))
      (node (ref "E5") (pin "8") (pinfunction "O_8") (pintype "output"))
      (node (ref "U$3") (pin "AV1") (pinfunction "1_AV1") (pintype "bidirectional"))
    )
    (net (code "57") (name "Net-(E12B-Q)") (class "Default")
      (node (ref "E12") (pin "9") (pinfunction "Q_9") (pintype "output"))
      (node (ref "U$3") (pin "AS2") (pinfunction "1_AS2") (pintype "bidirectional"))
    )
    (net (code "58") (name "Net-(E13A-I9)") (class "Default")
      (node (ref "E13") (pin "12") (pinfunction "I9_12") (pintype "passive"))
      (node (ref "E14") (pin "6") (pinfunction "E0_6") (pintype "passive"))
    )
    (net (code "59") (name "Net-(E13A-I10)") (class "Default")
      (node (ref "E13") (pin "11") (pinfunction "I10_11") (pintype "passive"))
      (node (ref "E14") (pin "8") (pinfunction "E1_8") (pintype "passive"))
    )
    (net (code "60") (name "Net-(E13A-I11)") (class "Default")
      (node (ref "E13") (pin "5") (pinfunction "I11_5") (pintype "input"))
      (node (ref "U$3") (pin "BF1") (pinfunction "1_BF1") (pintype "bidirectional"))
    )
    (net (code "61") (name "Net-(E13A-O)") (class "Default")
      (node (ref "E13") (pin "8") (pinfunction "O_8") (pintype "output"))
      (node (ref "E15") (pin "12") (pinfunction "D_12") (pintype "input"))
      (node (ref "U$3") (pin "BC1") (pinfunction "1_BC1") (pintype "bidirectional"))
    )
    (net (code "62") (name "Net-(E15A-Q)") (class "Default")
      (node (ref "E15") (pin "5") (pinfunction "Q_5") (pintype "output"))
      (node (ref "U$3") (pin "BJ2") (pinfunction "1_BJ2") (pintype "bidirectional"))
    )
    (net (code "63") (name "Net-(E15B-Q)") (class "Default")
      (node (ref "E15") (pin "9") (pinfunction "Q_9") (pintype "output"))
      (node (ref "U$3") (pin "BF2") (pinfunction "1_BF2") (pintype "bidirectional"))
    )
    (net (code "64") (name "Net-(E16A-I7)") (class "Default")
      (node (ref "E16") (pin "10") (pinfunction "I7_10") (pintype "input"))
      (node (ref "E20") (pin "10") (pinfunction "I2_10") (pintype "input"))
      (node (ref "E22") (pin "13") (pinfunction "I3_13") (pintype "input"))
      (node (ref "U$3") (pin "BN1") (pinfunction "1_BN1") (pintype "bidirectional"))
    )
    (net (code "65") (name "Net-(E16A-I9)") (class "Default")
      (node (ref "E16") (pin "12") (pinfunction "I9_12") (pintype "passive"))
      (node (ref "E17") (pin "6") (pinfunction "E0_6") (pintype "passive"))
    )
    (net (code "66") (name "Net-(E16A-I10)") (class "Default")
      (node (ref "E16") (pin "11") (pinfunction "I10_11") (pintype "passive"))
      (node (ref "E17") (pin "8") (pinfunction "E1_8") (pintype "passive"))
    )
    (net (code "67") (name "Net-(E16A-I11)") (class "Default")
      (node (ref "E16") (pin "5") (pinfunction "I11_5") (pintype "input"))
      (node (ref "U$3") (pin "BJ1") (pinfunction "1_BJ1") (pintype "bidirectional"))
    )
    (net (code "68") (name "Net-(E16A-O)") (class "Default")
      (node (ref "E16") (pin "8") (pinfunction "O_8") (pintype "output"))
      (node (ref "E18") (pin "12") (pinfunction "D_12") (pintype "input"))
      (node (ref "U$3") (pin "BK1") (pinfunction "1_BK1") (pintype "bidirectional"))
    )
    (net (code "69") (name "Net-(E18A-D)") (class "Default")
      (node (ref "E18") (pin "2") (pinfunction "D_2") (pintype "input"))
      (node (ref "E19") (pin "8") (pinfunction "O_8") (pintype "output"))
      (node (ref "U$3") (pin "BM1") (pinfunction "1_BM1") (pintype "bidirectional"))
    )
    (net (code "70") (name "Net-(E18A-Q)") (class "Default")
      (node (ref "E18") (pin "5") (pinfunction "Q_5") (pintype "output"))
      (node (ref "U$3") (pin "BM2") (pinfunction "1_BM2") (pintype "bidirectional"))
    )
    (net (code "71") (name "Net-(E18B-Q)") (class "Default")
      (node (ref "E18") (pin "9") (pinfunction "Q_9") (pintype "output"))
      (node (ref "U$3") (pin "BL2") (pinfunction "1_BL2") (pintype "bidirectional"))
    )
    (net (code "72") (name "Net-(E19A-I7)") (class "Default")
      (node (ref "E19") (pin "10") (pinfunction "I7_10") (pintype "input"))
      (node (ref "U$3") (pin "BL1") (pinfunction "1_BL1") (pintype "bidirectional"))
    )
    (net (code "73") (name "Net-(E19A-I9)") (class "Default")
      (node (ref "E19") (pin "12") (pinfunction "I9_12") (pintype "passive"))
      (node (ref "E20") (pin "6") (pinfunction "E0_6") (pintype "passive"))
    )
    (net (code "74") (name "Net-(E19A-I10)") (class "Default")
      (node (ref "E19") (pin "11") (pinfunction "I10_11") (pintype "passive"))
      (node (ref "E20") (pin "8") (pinfunction "E1_8") (pintype "passive"))
    )
    (net (code "75") (name "Net-(E19A-I11)") (class "Default")
      (node (ref "E19") (pin "5") (pinfunction "I11_5") (pintype "input"))
      (node (ref "U$3") (pin "BP1") (pinfunction "1_BP1") (pintype "bidirectional"))
    )
    (net (code "76") (name "Net-(E21B-D)") (class "Default")
      (node (ref "E21") (pin "12") (pinfunction "D_12") (pintype "input"))
      (node (ref "E22") (pin "8") (pinfunction "O_8") (pintype "output"))
      (node (ref "U$3") (pin "BS2") (pinfunction "1_BS2") (pintype "bidirectional"))
    )
    (net (code "77") (name "Net-(E21B-Q)") (class "Default")
      (node (ref "E21") (pin "9") (pinfunction "Q_9") (pintype "output"))
      (node (ref "U$3") (pin "BP2") (pinfunction "1_BP2") (pintype "bidirectional"))
    )
    (net (code "78") (name "Net-(E22A-I7)") (class "Default")
      (node (ref "E22") (pin "10") (pinfunction "I7_10") (pintype "input"))
      (node (ref "U$3") (pin "BR1") (pinfunction "1_BR1") (pintype "bidirectional"))
    )
    (net (code "79") (name "Net-(E22A-I9)") (class "Default")
      (node (ref "E22") (pin "12") (pinfunction "I9_12") (pintype "passive"))
      (node (ref "E23") (pin "6") (pinfunction "E0_6") (pintype "passive"))
    )
    (net (code "80") (name "Net-(E22A-I10)") (class "Default")
      (node (ref "E22") (pin "11") (pinfunction "I10_11") (pintype "passive"))
      (node (ref "E23") (pin "8") (pinfunction "E1_8") (pintype "passive"))
    )
    (net (code "81") (name "Net-(E22A-I11)") (class "Default")
      (node (ref "E22") (pin "5") (pinfunction "I11_5") (pintype "input"))
      (node (ref "U$3") (pin "BS1") (pinfunction "1_BS1") (pintype "bidirectional"))
    )
    (net (code "82") (name "Net-(E23A-I2)") (class "Default")
      (node (ref "E23") (pin "10") (pinfunction "I2_10") (pintype "input"))
      (node (ref "U$3") (pin "AP1") (pinfunction "1_AP1") (pintype "bidirectional"))
    )
    (net (code "83") (name "Net-(E23A-I6)") (class "Default")
      (node (ref "E23") (pin "13") (pinfunction "I6_13") (pintype "input"))
      (node (ref "U$3") (pin "BV2") (pinfunction "1_BV2") (pintype "bidirectional"))
    )
    (net (code "84") (name "VCC") (class "Default")
      (node (ref "C1") (pin "1") (pinfunction "1_1") (pintype "passive"))
      (node (ref "C10") (pin "1") (pinfunction "1_1") (pintype "passive"))
      (node (ref "C11") (pin "1") (pinfunction "1_1") (pintype "passive"))
      (node (ref "C12") (pin "1") (pinfunction "1_1") (pintype "passive"))
      (node (ref "C13") (pin "1") (pinfunction "1_1") (pintype "passive"))
      (node (ref "C14") (pin "1") (pinfunction "1_1") (pintype "passive"))
      (node (ref "C15") (pin "1") (pinfunction "1_1") (pintype "passive"))
      (node (ref "C16") (pin "1") (pinfunction "1_1") (pintype "passive"))
      (node (ref "C17") (pin "1") (pinfunction "1_1") (pintype "passive"))
      (node (ref "C18") (pin "1") (pinfunction "1_1") (pintype "passive"))
      (node (ref "C19") (pin "1") (pinfunction "1_1") (pintype "passive"))
      (node (ref "C2") (pin "1") (pinfunction "1_1") (pintype "passive"))
      (node (ref "C20") (pin "1") (pinfunction "1_1") (pintype "passive"))
      (node (ref "C21") (pin "1") (pinfunction "1_1") (pintype "passive"))
      (node (ref "C22") (pin "1") (pinfunction "1_1") (pintype "passive"))
      (node (ref "C23") (pin "1") (pinfunction "1_1") (pintype "passive"))
      (node (ref "C24") (pin "+") (pinfunction "+_+") (pintype "passive"))
      (node (ref "C3") (pin "1") (pinfunction "1_1") (pintype "passive"))
      (node (ref "C4") (pin "1") (pinfunction "1_1") (pintype "passive"))
      (node (ref "C5") (pin "1") (pinfunction "1_1") (pintype "passive"))
      (node (ref "C6") (pin "1") (pinfunction "1_1") (pintype "passive"))
      (node (ref "C7") (pin "1") (pinfunction "1_1") (pintype "passive"))
      (node (ref "C8") (pin "1") (pinfunction "1_1") (pintype "passive"))
      (node (ref "C9") (pin "1") (pinfunction "1_1") (pintype "passive"))
      (node (ref "R1") (pin "2") (pinfunction "2_2") (pintype "passive"))
      (node (ref "U$3") (pin "AA2") (pinfunction "1_AA2") (pintype "bidirectional"))
      (node (ref "U$3") (pin "BA2") (pinfunction "1_BA2") (pintype "bidirectional"))
    )
    (net (code "85") (name "unconnected-(E21A-Q-Pad5)") (class "Default")
      (node (ref "E21") (pin "5") (pinfunction "Q_5") (pintype "output"))
    )
    (net (code "86") (name "unconnected-(E21A-~{Q}-Pad6)") (class "Default")
      (node (ref "E21") (pin "6") (pinfunction "~{Q}_6") (pintype "output"))
    )
  )
)
